# fail.net
KiCad netlist of a schematic drawn in EAGLE
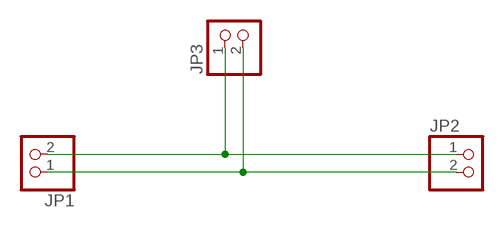
[diagram p0: schematic, sheet 1]

(export (version "E")
  (design (tool "Eeschema 10.0.6"))
  (components
    (comp (ref "JP1")
      (value "PINHD-1X2")
      (footprint "eagle-import:1X02")
      (libsource (lib "eagle-import") (part "PINHD-1X2"))
    )
    (comp (ref "JP2")
      (value "PINHD-1X2")
      (footprint "eagle-import:1X02")
      (libsource (lib "eagle-import") (part "PINHD-1X2"))
    )
    (comp (ref "JP3")
      (value "PINHD-1X2")
      (footprint "eagle-import:1X02")
      (libsource (lib "eagle-import") (part "PINHD-1X2"))
    )
  )
  (nets
    (net (code "1") (name "Net-(JP1-Pad1)") (class "Default")
      (node (ref "JP1") (pin "1") (pinfunction "1_1") (pintype "passive"))
      (node (ref "JP2") (pin "2") (pinfunction "2_2") (pintype "passive"))
      (node (ref "JP3") (pin "2") (pinfunction "2_2") (pintype "passive"))
    )
    (net (code "2") (name "Net-(JP1-Pad2)") (class "Default")
      (node (ref "JP1") (pin "2") (pinfunction "2_2") (pintype "passive"))
      (node (ref "JP2") (pin "1") (pinfunction "1_1") (pintype "passive"))
      (node (ref "JP3") (pin "1") (pinfunction "1_1") (pintype "passive"))
    )
  )
)
